# sch3.net
KiCad netlist of a schematic drawn in Altium Designer
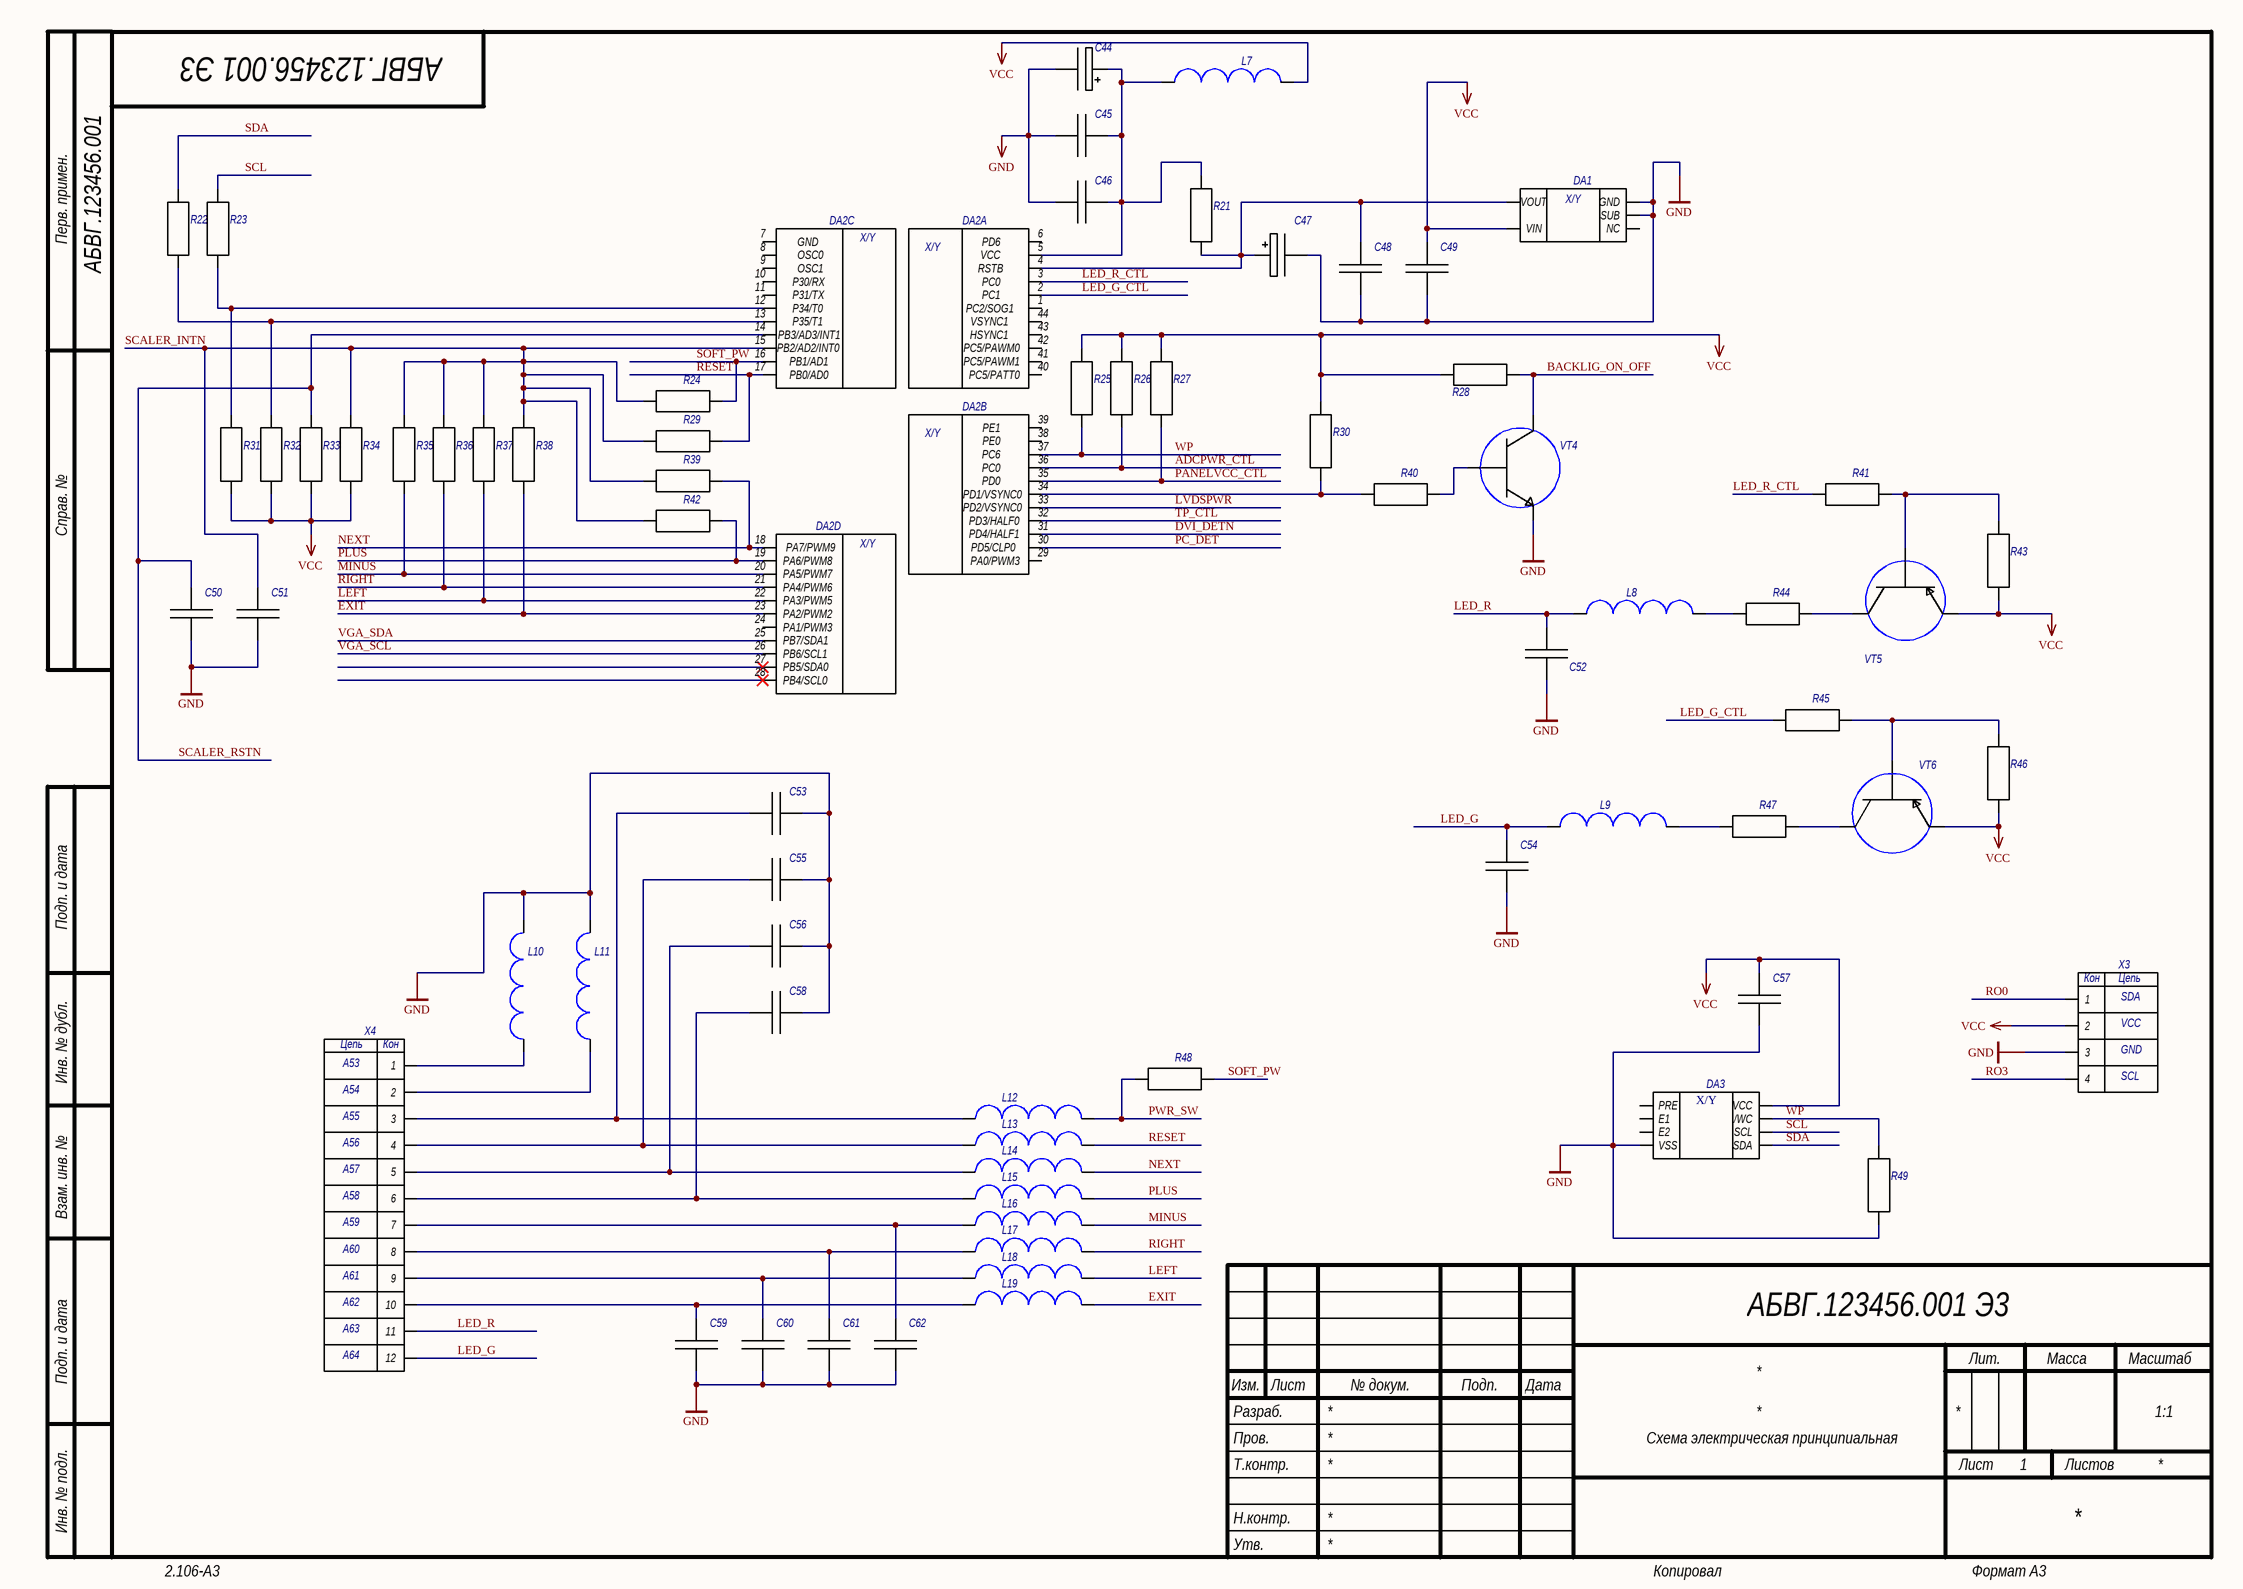
[diagram p0: sch3.SchDoc]

(export (version "E")
  (design (tool "Eeschema 10.0.6"))
  (components
    (comp (ref "C44")
      (value "*")
      (footprint "Capacitor 0805")
      (libsource (lib "k7shared") (part "Capacitor Duga"))
    )
    (comp (ref "C45")
      (value "*")
      (footprint "Capacitor 0805")
      (libsource (lib "k7shared") (part "Capacitor"))
    )
    (comp (ref "C46")
      (value "*")
      (footprint "Capacitor 0805")
      (libsource (lib "k7shared") (part "Capacitor"))
    )
    (comp (ref "C47")
      (value "*")
      (footprint "Capacitor 0805")
      (libsource (lib "k7shared") (part "Capacitor Duga"))
    )
    (comp (ref "C48")
      (value "*")
      (footprint "Capacitor 0805")
      (libsource (lib "k7shared") (part "Capacitor"))
    )
    (comp (ref "C49")
      (value "*")
      (footprint "Capacitor 0805")
      (libsource (lib "k7shared") (part "Capacitor"))
    )
    (comp (ref "C50")
      (value "*")
      (footprint "Capacitor 0805")
      (libsource (lib "k7shared") (part "Capacitor"))
    )
    (comp (ref "C51")
      (value "*")
      (footprint "Capacitor 0805")
      (libsource (lib "k7shared") (part "Capacitor"))
    )
    (comp (ref "C52")
      (value "*")
      (footprint "Capacitor 0805")
      (libsource (lib "k7shared") (part "Capacitor"))
    )
    (comp (ref "C53")
      (value "*")
      (footprint "Capacitor 0805")
      (libsource (lib "k7shared") (part "Capacitor"))
    )
    (comp (ref "C54")
      (value "*")
      (footprint "Capacitor 0805")
      (libsource (lib "k7shared") (part "Capacitor"))
    )
    (comp (ref "C55")
      (value "*")
      (footprint "Capacitor 0805")
      (libsource (lib "k7shared") (part "Capacitor"))
    )
    (comp (ref "C56")
      (value "*")
      (footprint "Capacitor 0805")
      (libsource (lib "k7shared") (part "Capacitor"))
    )
    (comp (ref "C57")
      (value "*")
      (footprint "Capacitor 0805")
      (libsource (lib "k7shared") (part "Capacitor"))
    )
    (comp (ref "C58")
      (value "*")
      (footprint "Capacitor 0805")
      (libsource (lib "k7shared") (part "Capacitor"))
    )
    (comp (ref "C59")
      (value "*")
      (footprint "Capacitor 0805")
      (libsource (lib "k7shared") (part "Capacitor"))
    )
    (comp (ref "C60")
      (value "*")
      (footprint "Capacitor 0805")
      (libsource (lib "k7shared") (part "Capacitor"))
    )
    (comp (ref "C61")
      (value "*")
      (footprint "Capacitor 0805")
      (libsource (lib "k7shared") (part "Capacitor"))
    )
    (comp (ref "C62")
      (value "*")
      (footprint "Capacitor 0805")
      (libsource (lib "k7shared") (part "Capacitor"))
    )
    (comp (ref "DA1") (value "IC103") (footprint "IC103_2") (libsource (lib "k7sch3") (part "IC103")))
    (comp (ref "DA2") (value "*") (footprint "NT68") (libsource (lib "k7sch3") (part "NT68")))
    (comp (ref "DA3") (value "*") (footprint "IC102") (libsource (lib "k7sch3") (part "IC102")))
    (comp (ref "L7") (value "*") (footprint "Inductor 2520") (libsource (lib "k7shared") (part "Inductor")))
    (comp (ref "L8") (value "*") (footprint "Inductor 2520") (libsource (lib "k7shared") (part "Inductor")))
    (comp (ref "L9") (value "*") (footprint "Inductor 2520") (libsource (lib "k7shared") (part "Inductor")))
    (comp (ref "L10") (value "*") (footprint "Inductor 2520") (libsource (lib "") (part "Inductor_1")))
    (comp (ref "L11") (value "*") (footprint "Inductor 2520") (libsource (lib "") (part "Inductor_1")))
    (comp (ref "L12") (value "*") (footprint "Inductor 2520") (libsource (lib "k7shared") (part "Inductor")))
    (comp (ref "L13") (value "*") (footprint "Inductor 2520") (libsource (lib "k7shared") (part "Inductor")))
    (comp (ref "L14") (value "*") (footprint "Inductor 2520") (libsource (lib "k7shared") (part "Inductor")))
    (comp (ref "L15") (value "*") (footprint "Inductor 2520") (libsource (lib "k7shared") (part "Inductor")))
    (comp (ref "L16") (value "*") (footprint "Inductor 2520") (libsource (lib "k7shared") (part "Inductor")))
    (comp (ref "L17") (value "*") (footprint "Inductor 2520") (libsource (lib "k7shared") (part "Inductor")))
    (comp (ref "L18") (value "*") (footprint "Inductor 2520") (libsource (lib "k7shared") (part "Inductor")))
    (comp (ref "L19") (value "*") (footprint "Inductor 2520") (libsource (lib "k7shared") (part "Inductor")))
    (comp (ref "R21") (value "*") (footprint "Resistor 1206") (libsource (lib "k7shared") (part "Resistor")))
    (comp (ref "R22") (value "*") (footprint "Resistor 1206") (libsource (lib "k7shared") (part "Resistor")))
    (comp (ref "R23") (value "*") (footprint "Resistor 1206") (libsource (lib "k7shared") (part "Resistor")))
    (comp (ref "R24") (value "*") (footprint "Resistor 1206") (libsource (lib "k7shared") (part "Resistor")))
    (comp (ref "R25") (value "*") (footprint "Resistor 1206") (libsource (lib "k7shared") (part "Resistor")))
    (comp (ref "R26") (value "*") (footprint "Resistor 1206") (libsource (lib "k7shared") (part "Resistor")))
    (comp (ref "R27") (value "*") (footprint "Resistor 1206") (libsource (lib "k7shared") (part "Resistor")))
    (comp (ref "R28") (value "*") (footprint "Resistor 1206") (libsource (lib "k7shared") (part "Resistor")))
    (comp (ref "R29") (value "*") (footprint "Resistor 1206") (libsource (lib "k7shared") (part "Resistor")))
    (comp (ref "R30") (value "*") (footprint "Resistor 1206") (libsource (lib "k7shared") (part "Resistor")))
    (comp (ref "R31") (value "*") (footprint "Resistor 1206") (libsource (lib "k7shared") (part "Resistor")))
    (comp (ref "R32") (value "*") (footprint "Resistor 1206") (libsource (lib "k7shared") (part "Resistor")))
    (comp (ref "R33") (value "*") (footprint "Resistor 1206") (libsource (lib "k7shared") (part "Resistor")))
    (comp (ref "R34") (value "*") (footprint "Resistor 1206") (libsource (lib "k7shared") (part "Resistor")))
    (comp (ref "R35") (value "*") (footprint "Resistor 1206") (libsource (lib "k7shared") (part "Resistor")))
    (comp (ref "R36") (value "*") (footprint "Resistor 1206") (libsource (lib "k7shared") (part "Resistor")))
    (comp (ref "R37") (value "*") (footprint "Resistor 1206") (libsource (lib "k7shared") (part "Resistor")))
    (comp (ref "R38") (value "*") (footprint "Resistor 1206") (libsource (lib "k7shared") (part "Resistor")))
    (comp (ref "R39") (value "*") (footprint "Resistor 1206") (libsource (lib "k7shared") (part "Resistor")))
    (comp (ref "R40") (value "*") (footprint "Resistor 1206") (libsource (lib "k7shared") (part "Resistor")))
    (comp (ref "R41") (value "*") (footprint "Resistor 1206") (libsource (lib "k7shared") (part "Resistor")))
    (comp (ref "R42") (value "*") (footprint "Resistor 1206") (libsource (lib "k7shared") (part "Resistor")))
    (comp (ref "R43") (value "*") (footprint "Resistor 1206") (libsource (lib "k7shared") (part "Resistor")))
    (comp (ref "R44") (value "*") (footprint "Resistor 1206") (libsource (lib "k7shared") (part "Resistor")))
    (comp (ref "R45") (value "*") (footprint "Resistor 1206") (libsource (lib "k7shared") (part "Resistor")))
    (comp (ref "R46") (value "*") (footprint "Resistor 1206") (libsource (lib "k7shared") (part "Resistor")))
    (comp (ref "R47") (value "*") (footprint "Resistor 1206") (libsource (lib "k7shared") (part "Resistor")))
    (comp (ref "R48") (value "*") (footprint "Resistor 1206") (libsource (lib "k7shared") (part "Resistor")))
    (comp (ref "R49") (value "*") (footprint "Resistor 1206") (libsource (lib "k7shared") (part "Resistor")))
    (comp (ref "VT4")
      (value "*")
      (footprint "Transistor 1")
      (libsource (lib "k7shared") (part "Transistor 1"))
    )
    (comp (ref "VT5")
      (value "*")
      (footprint "Transistor 1")
      (libsource (lib "k7shared") (part "Transistor 2"))
    )
    (comp (ref "VT6")
      (value "*")
      (footprint "Transistor 1")
      (libsource (lib "k7shared") (part "Transistor 2"))
    )
    (comp (ref "X3") (value "*") (footprint "BUSES") (libsource (lib "k7sch3") (part "J102")))
    (comp (ref "X4") (value "*") (footprint "J101") (libsource (lib "k7sch3") (part "J101")))
  )
  (nets
    (net (code "1") (name "/ADCPWR_CTL") (class "Default")
      (node (ref "DA2") (pin "36") (pinfunction "PC0_36") (pintype "passive"))
      (node (ref "R26") (pin "1") (pinfunction "1_1") (pintype "passive"))
    )
    (net (code "2") (name "/BACKLIG_ON_OFF") (class "Default")
      (node (ref "R28") (pin "2") (pinfunction "2_2") (pintype "passive"))
      (node (ref "VT4") (pin "2") (pinfunction "EMITTER_2") (pintype "passive"))
    )
    (net (code "3") (name "/DVI_DETN") (class "Default")
      (node (ref "DA2") (pin "31") (pinfunction "PD4/HALF1_31") (pintype "passive"))
    )
    (net (code "4") (name "/EXIT") (class "Default")
      (node (ref "DA2") (pin "23") (pinfunction "PA2/PWM2_23") (pintype "passive"))
      (node (ref "L19") (pin "2") (pinfunction "2_2") (pintype "passive"))
      (node (ref "R38") (pin "1") (pinfunction "1_1") (pintype "passive"))
    )
    (net (code "5") (name "/LED_G") (class "Default")
      (node (ref "C54") (pin "2") (pinfunction "2_2") (pintype "passive"))
      (node (ref "L9") (pin "1") (pinfunction "1_1") (pintype "passive"))
      (node (ref "X4") (pin "12") (pinfunction "12_12") (pintype "passive"))
    )
    (net (code "6") (name "/LED_G_CTL") (class "Default")
      (node (ref "DA2") (pin "2") (pinfunction "PC1_2") (pintype "passive"))
      (node (ref "R45") (pin "1") (pinfunction "1_1") (pintype "passive"))
    )
    (net (code "7") (name "/LED_R") (class "Default")
      (node (ref "C52") (pin "2") (pinfunction "2_2") (pintype "passive"))
      (node (ref "L8") (pin "1") (pinfunction "1_1") (pintype "passive"))
      (node (ref "X4") (pin "11") (pinfunction "11_11") (pintype "passive"))
    )
    (net (code "8") (name "/LED_R_CTL") (class "Default")
      (node (ref "DA2") (pin "3") (pinfunction "PC0_3") (pintype "passive"))
      (node (ref "R41") (pin "1") (pinfunction "1_1") (pintype "passive"))
    )
    (net (code "9") (name "/LEFT") (class "Default")
      (node (ref "DA2") (pin "22") (pinfunction "PA3/PWM5_22") (pintype "passive"))
      (node (ref "L18") (pin "2") (pinfunction "2_2") (pintype "passive"))
      (node (ref "R37") (pin "1") (pinfunction "1_1") (pintype "passive"))
    )
    (net (code "10") (name "/LVDSPWR") (class "Default")
      (node (ref "DA2") (pin "33") (pinfunction "PD2/VSYNC0_33") (pintype "passive"))
    )
    (net (code "11") (name "/MINUS") (class "Default")
      (node (ref "DA2") (pin "20") (pinfunction "PA5/PWM7_20") (pintype "passive"))
      (node (ref "L16") (pin "2") (pinfunction "2_2") (pintype "passive"))
      (node (ref "R35") (pin "1") (pinfunction "1_1") (pintype "passive"))
    )
    (net (code "12") (name "/NEXT") (class "Default")
      (node (ref "DA2") (pin "18") (pinfunction "PA7/PWM9_18") (pintype "passive"))
      (node (ref "L14") (pin "2") (pinfunction "2_2") (pintype "passive"))
      (node (ref "R39") (pin "2") (pinfunction "2_2") (pintype "passive"))
    )
    (net (code "13") (name "/PANELVCC_CTL") (class "Default")
      (node (ref "DA2") (pin "35") (pinfunction "PD0_35") (pintype "passive"))
      (node (ref "R27") (pin "1") (pinfunction "1_1") (pintype "passive"))
    )
    (net (code "14") (name "/PC_DET") (class "Default")
      (node (ref "DA2") (pin "30") (pinfunction "PD5/CLP0_30") (pintype "passive"))
    )
    (net (code "15") (name "/PLUS") (class "Default")
      (node (ref "DA2") (pin "19") (pinfunction "PA6/PWM8_19") (pintype "passive"))
      (node (ref "L15") (pin "2") (pinfunction "2_2") (pintype "passive"))
      (node (ref "R42") (pin "2") (pinfunction "2_2") (pintype "passive"))
    )
    (net (code "16") (name "/PWR_SW") (class "Default")
      (node (ref "L12") (pin "2") (pinfunction "2_2") (pintype "passive"))
      (node (ref "R48") (pin "1") (pinfunction "1_1") (pintype "passive"))
    )
    (net (code "17") (name "/RESET") (class "Default")
      (node (ref "DA2") (pin "17") (pinfunction "PB0/AD0_17") (pintype "passive"))
      (node (ref "L13") (pin "2") (pinfunction "2_2") (pintype "passive"))
      (node (ref "R29") (pin "2") (pinfunction "2_2") (pintype "passive"))
    )
    (net (code "18") (name "/RIGHT") (class "Default")
      (node (ref "DA2") (pin "21") (pinfunction "PA4/PWM6_21") (pintype "passive"))
      (node (ref "L17") (pin "2") (pinfunction "2_2") (pintype "passive"))
      (node (ref "R36") (pin "1") (pinfunction "1_1") (pintype "passive"))
    )
    (net (code "19") (name "/RO0") (class "Default")
      (node (ref "X3") (pin "1") (pinfunction "1_1") (pintype "passive"))
    )
    (net (code "20") (name "/RO3") (class "Default")
      (node (ref "X3") (pin "4") (pinfunction "4_4") (pintype "passive"))
    )
    (net (code "21") (name "/SCALER_INTN") (class "Default")
      (node (ref "C51") (pin "2") (pinfunction "2_2") (pintype "passive"))
      (node (ref "DA2") (pin "15") (pinfunction "PB2/AD2/INT0_15") (pintype "passive"))
      (node (ref "R24") (pin "1") (pinfunction "1_1") (pintype "passive"))
      (node (ref "R29") (pin "1") (pinfunction "1_1") (pintype "passive"))
      (node (ref "R34") (pin "2") (pinfunction "2_2") (pintype "passive"))
      (node (ref "R35") (pin "2") (pinfunction "2_2") (pintype "passive"))
      (node (ref "R36") (pin "2") (pinfunction "2_2") (pintype "passive"))
      (node (ref "R37") (pin "2") (pinfunction "2_2") (pintype "passive"))
      (node (ref "R38") (pin "2") (pinfunction "2_2") (pintype "passive"))
      (node (ref "R39") (pin "1") (pinfunction "1_1") (pintype "passive"))
      (node (ref "R42") (pin "1") (pinfunction "1_1") (pintype "passive"))
    )
    (net (code "22") (name "/SCALER_RSTN") (class "Default")
      (node (ref "C50") (pin "2") (pinfunction "2_2") (pintype "passive"))
      (node (ref "DA2") (pin "14") (pinfunction "PB3/AD3/INT1_14") (pintype "passive"))
      (node (ref "R33") (pin "2") (pinfunction "2_2") (pintype "passive"))
    )
    (net (code "23") (name "/SCL") (class "Default")
      (node (ref "DA3") (pin "7") (pinfunction "SCL_7") (pintype "passive"))
      (node (ref "R23") (pin "2") (pinfunction "2_2") (pintype "passive"))
    )
    (net (code "24") (name "/SDA") (class "Default")
      (node (ref "DA3") (pin "8") (pinfunction "SDA_8") (pintype "passive"))
      (node (ref "R22") (pin "2") (pinfunction "2_2") (pintype "passive"))
    )
    (net (code "25") (name "/SOFT_PW") (class "Default")
      (node (ref "DA2") (pin "16") (pinfunction "PB1/AD1_16") (pintype "passive"))
      (node (ref "R24") (pin "2") (pinfunction "2_2") (pintype "passive"))
      (node (ref "R48") (pin "2") (pinfunction "2_2") (pintype "passive"))
    )
    (net (code "26") (name "/TP_CTL") (class "Default")
      (node (ref "DA2") (pin "32") (pinfunction "PD3/HALF0_32") (pintype "passive"))
    )
    (net (code "27") (name "/VGA_SCL") (class "Default")
      (node (ref "DA2") (pin "26") (pinfunction "PB6/SCL1_26") (pintype "passive"))
    )
    (net (code "28") (name "/VGA_SDA") (class "Default")
      (node (ref "DA2") (pin "25") (pinfunction "PB7/SDA1_25") (pintype "passive"))
    )
    (net (code "29") (name "/WP") (class "Default")
      (node (ref "DA2") (pin "37") (pinfunction "PC6_37") (pintype "passive"))
      (node (ref "DA3") (pin "6") (pinfunction "/WC_6") (pintype "passive"))
      (node (ref "R25") (pin "1") (pinfunction "1_1") (pintype "passive"))
      (node (ref "R49") (pin "2") (pinfunction "2_2") (pintype "passive"))
    )
    (net (code "30") (name "GND") (class "Default")
      (node (ref "C44") (pin "1") (pinfunction "1_1") (pintype "passive"))
      (node (ref "C45") (pin "2") (pinfunction "2_2") (pintype "passive"))
      (node (ref "C46") (pin "2") (pinfunction "2_2") (pintype "passive"))
      (node (ref "C47") (pin "1") (pinfunction "1_1") (pintype "passive"))
      (node (ref "C48") (pin "2") (pinfunction "2_2") (pintype "passive"))
      (node (ref "C49") (pin "2") (pinfunction "2_2") (pintype "passive"))
      (node (ref "C50") (pin "1") (pinfunction "1_1") (pintype "passive"))
      (node (ref "C51") (pin "1") (pinfunction "1_1") (pintype "passive"))
      (node (ref "C52") (pin "1") (pinfunction "1_1") (pintype "passive"))
      (node (ref "C53") (pin "1") (pinfunction "1_1") (pintype "passive"))
      (node (ref "C54") (pin "1") (pinfunction "1_1") (pintype "passive"))
      (node (ref "C55") (pin "1") (pinfunction "1_1") (pintype "passive"))
      (node (ref "C56") (pin "1") (pinfunction "1_1") (pintype "passive"))
      (node (ref "C57") (pin "1") (pinfunction "1_1") (pintype "passive"))
      (node (ref "C58") (pin "1") (pinfunction "1_1") (pintype "passive"))
      (node (ref "C59") (pin "1") (pinfunction "1_1") (pintype "passive"))
      (node (ref "C60") (pin "1") (pinfunction "1_1") (pintype "passive"))
      (node (ref "C61") (pin "1") (pinfunction "1_1") (pintype "passive"))
      (node (ref "C62") (pin "1") (pinfunction "1_1") (pintype "passive"))
      (node (ref "DA1") (pin "1") (pinfunction "GND_1") (pintype "passive"))
      (node (ref "DA1") (pin "2") (pinfunction "SUB_2") (pintype "passive"))
      (node (ref "DA3") (pin "4") (pinfunction "VSS_4") (pintype "passive"))
      (node (ref "L10") (pin "2") (pinfunction "2_2") (pintype "passive"))
      (node (ref "L11") (pin "2") (pinfunction "2_2") (pintype "passive"))
      (node (ref "R49") (pin "1") (pinfunction "1_1") (pintype "passive"))
      (node (ref "VT4") (pin "1") (pinfunction "KOLLECTOR_1") (pintype "passive"))
      (node (ref "X3") (pin "3") (pinfunction "3_3") (pintype "passive"))
    )
    (net (code "31") (name "Net-(C53-Pad2)") (class "Default")
      (node (ref "C53") (pin "2") (pinfunction "2_2") (pintype "passive"))
      (node (ref "L12") (pin "1") (pinfunction "1_1") (pintype "passive"))
      (node (ref "X4") (pin "3") (pinfunction "3_3") (pintype "passive"))
    )
    (net (code "32") (name "Net-(C55-Pad2)") (class "Default")
      (node (ref "C55") (pin "2") (pinfunction "2_2") (pintype "passive"))
      (node (ref "L13") (pin "1") (pinfunction "1_1") (pintype "passive"))
      (node (ref "X4") (pin "4") (pinfunction "4_4") (pintype "passive"))
    )
    (net (code "33") (name "Net-(C56-Pad2)") (class "Default")
      (node (ref "C56") (pin "2") (pinfunction "2_2") (pintype "passive"))
      (node (ref "L14") (pin "1") (pinfunction "1_1") (pintype "passive"))
      (node (ref "X4") (pin "5") (pinfunction "5_5") (pintype "passive"))
    )
    (net (code "34") (name "Net-(C58-Pad2)") (class "Default")
      (node (ref "C58") (pin "2") (pinfunction "2_2") (pintype "passive"))
      (node (ref "L15") (pin "1") (pinfunction "1_1") (pintype "passive"))
      (node (ref "X4") (pin "6") (pinfunction "6_6") (pintype "passive"))
    )
    (net (code "35") (name "Net-(C59-Pad2)") (class "Default")
      (node (ref "C59") (pin "2") (pinfunction "2_2") (pintype "passive"))
      (node (ref "L19") (pin "1") (pinfunction "1_1") (pintype "passive"))
      (node (ref "X4") (pin "10") (pinfunction "10_10") (pintype "passive"))
    )
    (net (code "36") (name "Net-(C60-Pad2)") (class "Default")
      (node (ref "C60") (pin "2") (pinfunction "2_2") (pintype "passive"))
      (node (ref "L18") (pin "1") (pinfunction "1_1") (pintype "passive"))
      (node (ref "X4") (pin "9") (pinfunction "9_9") (pintype "passive"))
    )
    (net (code "37") (name "Net-(C61-Pad2)") (class "Default")
      (node (ref "C61") (pin "2") (pinfunction "2_2") (pintype "passive"))
      (node (ref "L17") (pin "1") (pinfunction "1_1") (pintype "passive"))
      (node (ref "X4") (pin "8") (pinfunction "8_8") (pintype "passive"))
    )
    (net (code "38") (name "Net-(C62-Pad2)") (class "Default")
      (node (ref "C62") (pin "2") (pinfunction "2_2") (pintype "passive"))
      (node (ref "L16") (pin "1") (pinfunction "1_1") (pintype "passive"))
      (node (ref "X4") (pin "7") (pinfunction "7_7") (pintype "passive"))
    )
    (net (code "39") (name "Net-(DA1-VOUT)") (class "Default")
      (node (ref "C47") (pin "2") (pinfunction "2_2") (pintype "passive"))
      (node (ref "C48") (pin "1") (pinfunction "1_1") (pintype "passive"))
      (node (ref "DA1") (pin "4") (pinfunction "VOUT_4") (pintype "passive"))
      (node (ref "DA2") (pin "4") (pinfunction "RSTB_4") (pintype "passive"))
      (node (ref "R21") (pin "1") (pinfunction "1_1") (pintype "passive"))
    )
    (net (code "40") (name "Net-(DA2A-VCC)") (class "Default")
      (node (ref "C44") (pin "2") (pinfunction "2_2") (pintype "passive"))
      (node (ref "C45") (pin "1") (pinfunction "1_1") (pintype "passive"))
      (node (ref "C46") (pin "1") (pinfunction "1_1") (pintype "passive"))
      (node (ref "DA2") (pin "5") (pinfunction "VCC_5") (pintype "passive"))
      (node (ref "L7") (pin "1") (pinfunction "1_1") (pintype "passive"))
      (node (ref "R21") (pin "2") (pinfunction "2_2") (pintype "passive"))
    )
    (net (code "41") (name "Net-(DA2B-PD1{slash}VSYNC0)") (class "Default")
      (node (ref "DA2") (pin "34") (pinfunction "PD1/VSYNC0_34") (pintype "passive"))
      (node (ref "R30") (pin "1") (pinfunction "1_1") (pintype "passive"))
      (node (ref "R40") (pin "1") (pinfunction "1_1") (pintype "passive"))
    )
    (net (code "42") (name "Net-(DA2C-P34{slash}T0)") (class "Default")
      (node (ref "DA2") (pin "12") (pinfunction "P34/T0_12") (pintype "passive"))
      (node (ref "R23") (pin "1") (pinfunction "1_1") (pintype "passive"))
      (node (ref "R31") (pin "2") (pinfunction "2_2") (pintype "passive"))
    )
    (net (code "43") (name "Net-(DA2C-P35{slash}T1)") (class "Default")
      (node (ref "DA2") (pin "13") (pinfunction "P35/T1_13") (pintype "passive"))
      (node (ref "R22") (pin "1") (pinfunction "1_1") (pintype "passive"))
      (node (ref "R32") (pin "2") (pinfunction "2_2") (pintype "passive"))
    )
    (net (code "44") (name "Net-(L8-Pad2)") (class "Default")
      (node (ref "L8") (pin "2") (pinfunction "2_2") (pintype "passive"))
      (node (ref "R44") (pin "1") (pinfunction "1_1") (pintype "passive"))
    )
    (net (code "45") (name "Net-(L9-Pad2)") (class "Default")
      (node (ref "L9") (pin "2") (pinfunction "2_2") (pintype "passive"))
      (node (ref "R47") (pin "1") (pinfunction "1_1") (pintype "passive"))
    )
    (net (code "46") (name "Net-(L10-Pad1)") (class "Default")
      (node (ref "L10") (pin "1") (pinfunction "1_1") (pintype "passive"))
      (node (ref "X4") (pin "1") (pinfunction "1_1") (pintype "passive"))
    )
    (net (code "47") (name "Net-(L11-Pad1)") (class "Default")
      (node (ref "L11") (pin "1") (pinfunction "1_1") (pintype "passive"))
      (node (ref "X4") (pin "2") (pinfunction "2_2") (pintype "passive"))
    )
    (net (code "48") (name "Net-(VT4-BAZA)") (class "Default")
      (node (ref "R40") (pin "2") (pinfunction "2_2") (pintype "passive"))
      (node (ref "VT4") (pin "3") (pinfunction "BAZA_3") (pintype "passive"))
    )
    (net (code "49") (name "Net-(VT5-BAZA)") (class "Default")
      (node (ref "R41") (pin "2") (pinfunction "2_2") (pintype "passive"))
      (node (ref "R43") (pin "2") (pinfunction "2_2") (pintype "passive"))
      (node (ref "VT5") (pin "3") (pinfunction "BAZA_3") (pintype "passive"))
    )
    (net (code "50") (name "Net-(VT5-KOLLECTOR)") (class "Default")
      (node (ref "R44") (pin "2") (pinfunction "2_2") (pintype "passive"))
      (node (ref "VT5") (pin "1") (pinfunction "KOLLECTOR_1") (pintype "passive"))
    )
    (net (code "51") (name "Net-(VT6-BAZA)") (class "Default")
      (node (ref "R45") (pin "2") (pinfunction "2_2") (pintype "passive"))
      (node (ref "R46") (pin "2") (pinfunction "2_2") (pintype "passive"))
      (node (ref "VT6") (pin "3") (pinfunction "BAZA_3") (pintype "passive"))
    )
    (net (code "52") (name "Net-(VT6-KOLLECTOR)") (class "Default")
      (node (ref "R47") (pin "2") (pinfunction "2_2") (pintype "passive"))
      (node (ref "VT6") (pin "1") (pinfunction "KOLLECTOR_1") (pintype "passive"))
    )
    (net (code "53") (name "VCC") (class "Default")
      (node (ref "C49") (pin "1") (pinfunction "1_1") (pintype "passive"))
      (node (ref "C57") (pin "2") (pinfunction "2_2") (pintype "passive"))
      (node (ref "DA1") (pin "5") (pinfunction "VIN_5") (pintype "passive"))
      (node (ref "DA3") (pin "5") (pinfunction "VCC_5") (pintype "passive"))
      (node (ref "L7") (pin "2") (pinfunction "2_2") (pintype "passive"))
      (node (ref "R25") (pin "2") (pinfunction "2_2") (pintype "passive"))
      (node (ref "R26") (pin "2") (pinfunction "2_2") (pintype "passive"))
      (node (ref "R27") (pin "2") (pinfunction "2_2") (pintype "passive"))
      (node (ref "R28") (pin "1") (pinfunction "1_1") (pintype "passive"))
      (node (ref "R30") (pin "2") (pinfunction "2_2") (pintype "passive"))
      (node (ref "R31") (pin "1") (pinfunction "1_1") (pintype "passive"))
      (node (ref "R32") (pin "1") (pinfunction "1_1") (pintype "passive"))
      (node (ref "R33") (pin "1") (pinfunction "1_1") (pintype "passive"))
      (node (ref "R34") (pin "1") (pinfunction "1_1") (pintype "passive"))
      (node (ref "R43") (pin "1") (pinfunction "1_1") (pintype "passive"))
      (node (ref "R46") (pin "1") (pinfunction "1_1") (pintype "passive"))
      (node (ref "VT5") (pin "2") (pinfunction "EMITTER_2") (pintype "passive"))
      (node (ref "VT6") (pin "2") (pinfunction "EMITTER_2") (pintype "passive"))
      (node (ref "X3") (pin "2") (pinfunction "2_2") (pintype "passive"))
    )
    (net (code "54") (name "unconnected-(DA1-NC-Pad3)") (class "Default")
      (node (ref "DA1") (pin "3") (pinfunction "NC_3") (pintype "passive"))
    )
    (net (code "55") (name "unconnected-(DA2A-HSYNC1-Pad43)") (class "Default")
      (node (ref "DA2") (pin "43") (pinfunction "HSYNC1_43") (pintype "passive"))
    )
    (net (code "56") (name "unconnected-(DA2A-PC2{slash}SOG1-Pad1)") (class "Default")
      (node (ref "DA2") (pin "1") (pinfunction "PC2/SOG1_1") (pintype "passive"))
    )
    (net (code "57") (name "unconnected-(DA2A-PC5{slash}PATT0-Pad40)") (class "Default")
      (node (ref "DA2") (pin "40") (pinfunction "PC5/PATT0_40") (pintype "passive"))
    )
    (net (code "58") (name "unconnected-(DA2A-PC5{slash}PAWM0-Pad42)") (class "Default")
      (node (ref "DA2") (pin "42") (pinfunction "PC5/PAWM0_42") (pintype "passive"))
    )
    (net (code "59") (name "unconnected-(DA2A-PC5{slash}PAWM1-Pad41)") (class "Default")
      (node (ref "DA2") (pin "41") (pinfunction "PC5/PAWM1_41") (pintype "passive"))
    )
    (net (code "60") (name "unconnected-(DA2A-PD6-Pad6)") (class "Default")
      (node (ref "DA2") (pin "6") (pinfunction "PD6_6") (pintype "passive"))
    )
    (net (code "61") (name "unconnected-(DA2A-VSYNC1-Pad44)") (class "Default")
      (node (ref "DA2") (pin "44") (pinfunction "VSYNC1_44") (pintype "passive"))
    )
    (net (code "62") (name "unconnected-(DA2B-PA0{slash}PWM3-Pad29)") (class "Default")
      (node (ref "DA2") (pin "29") (pinfunction "PA0/PWM3_29") (pintype "passive"))
    )
    (net (code "63") (name "unconnected-(DA2B-PE0-Pad38)") (class "Default")
      (node (ref "DA2") (pin "38") (pinfunction "PE0_38") (pintype "passive"))
    )
    (net (code "64") (name "unconnected-(DA2B-PE1-Pad39)") (class "Default")
      (node (ref "DA2") (pin "39") (pinfunction "PE1_39") (pintype "passive"))
    )
    (net (code "65") (name "unconnected-(DA2C-GND-Pad7)") (class "Default")
      (node (ref "DA2") (pin "7") (pinfunction "GND_7") (pintype "passive"))
    )
    (net (code "66") (name "unconnected-(DA2C-OSC0-Pad8)") (class "Default")
      (node (ref "DA2") (pin "8") (pinfunction "OSC0_8") (pintype "passive"))
    )
    (net (code "67") (name "unconnected-(DA2C-OSC1-Pad9)") (class "Default")
      (node (ref "DA2") (pin "9") (pinfunction "OSC1_9") (pintype "passive"))
    )
    (net (code "68") (name "unconnected-(DA2C-P30{slash}RX-Pad10)") (class "Default")
      (node (ref "DA2") (pin "10") (pinfunction "P30/RX_10") (pintype "passive"))
    )
    (net (code "69") (name "unconnected-(DA2C-P31{slash}TX-Pad11)") (class "Default")
      (node (ref "DA2") (pin "11") (pinfunction "P31/TX_11") (pintype "passive"))
    )
    (net (code "70") (name "unconnected-(DA2D-PA1{slash}PWM3-Pad24)") (class "Default")
      (node (ref "DA2") (pin "24") (pinfunction "PA1/PWM3_24") (pintype "passive"))
    )
    (net (code "71") (name "unconnected-(DA2D-PB4{slash}SCL0-Pad28)") (class "Default")
      (node (ref "DA2") (pin "28") (pinfunction "PB4/SCL0_28") (pintype "passive+no_connect"))
    )
    (net (code "72") (name "unconnected-(DA2D-PB5{slash}SDA0-Pad27)") (class "Default")
      (node (ref "DA2") (pin "27") (pinfunction "PB5/SDA0_27") (pintype "passive+no_connect"))
    )
    (net (code "73") (name "unconnected-(DA3-E1-Pad2)") (class "Default")
      (node (ref "DA3") (pin "2") (pinfunction "E1_2") (pintype "passive"))
    )
    (net (code "74") (name "unconnected-(DA3-E2-Pad3)") (class "Default")
      (node (ref "DA3") (pin "3") (pinfunction "E2_3") (pintype "passive"))
    )
    (net (code "75") (name "unconnected-(DA3-PRE-Pad1)") (class "Default")
      (node (ref "DA3") (pin "1") (pinfunction "PRE_1") (pintype "passive"))
    )
  )
)
